# design.net
KiCad netlist of a schematic drawn in EasyEDA Pro
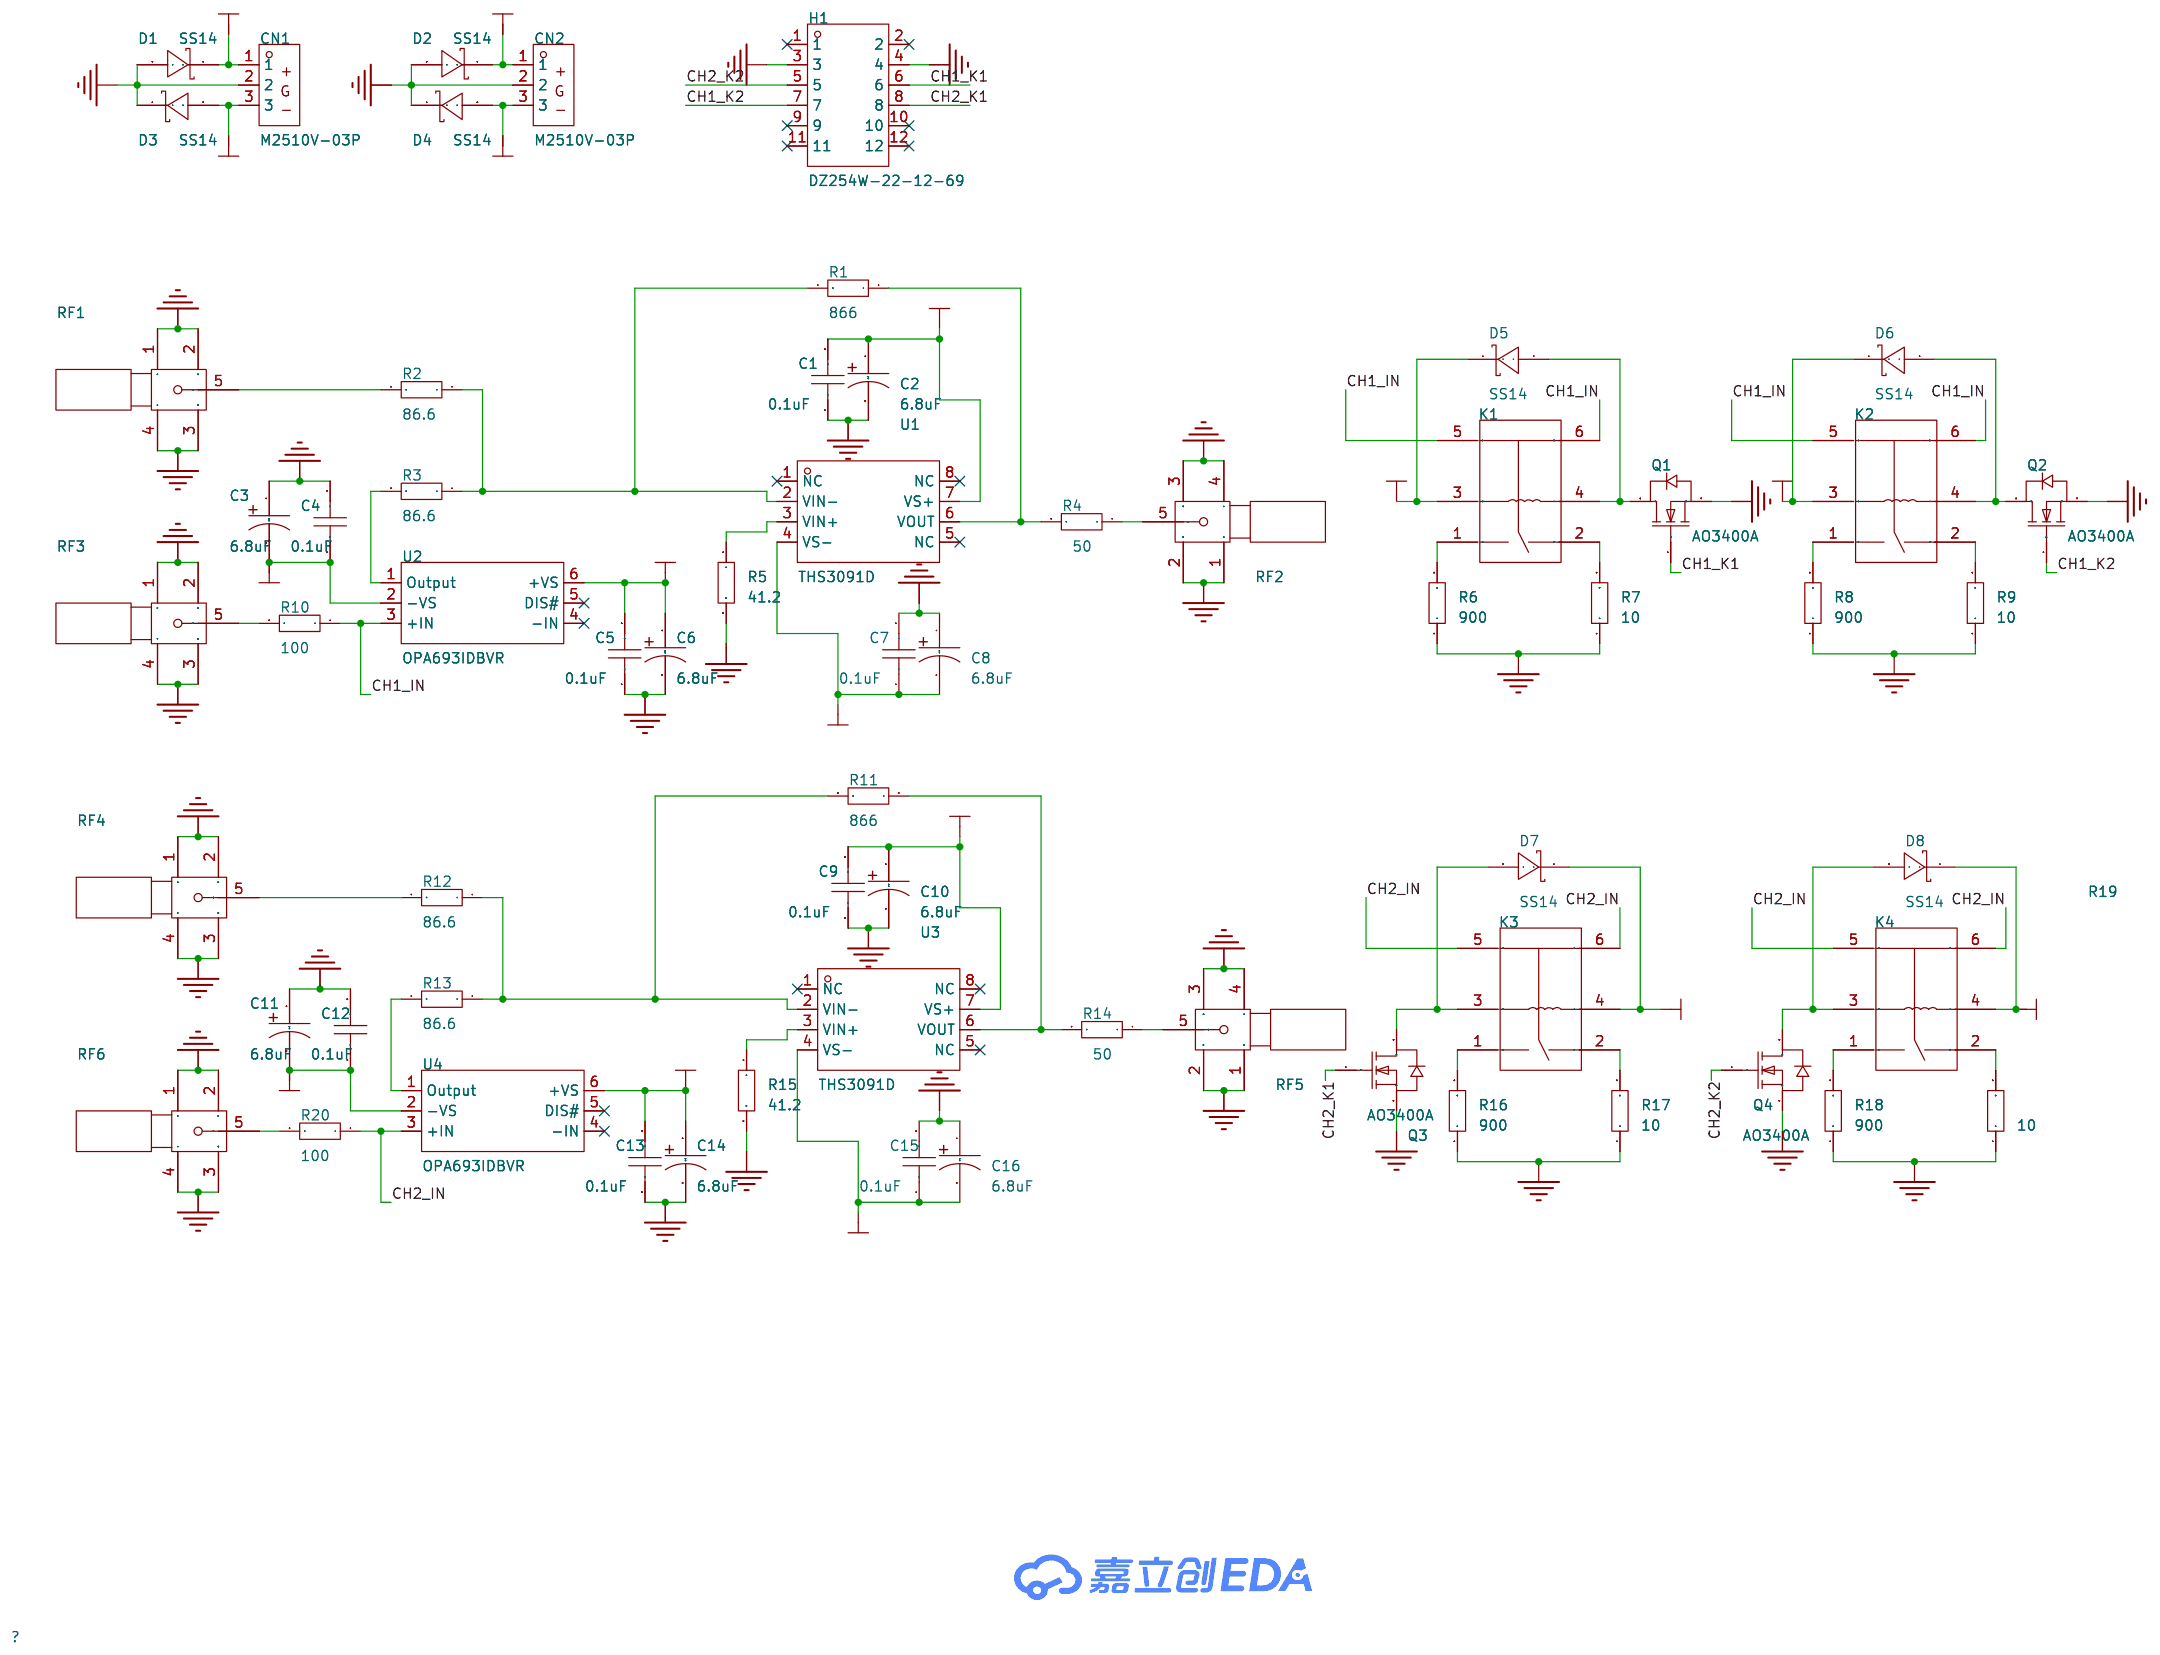
[diagram p0: schematic sheet]

(export (version "E")
  (design (tool "Eeschema 10.0.6"))
  (components
    (comp (ref "C1")
      (value "0.1uF")
      (footprint "easyedapro:C0603")
      (libsource (lib "easyedapro") (part "CapAcitance"))
    )
    (comp (ref "C2")
      (value "6.8uF")
      (footprint "easyedapro:CAP-SMD_L3.5-W2.8-R-RD")
      (description "容值:6.8uF;精度:±10%;额定电压:25V;等效串联电阻:2.8Ω@100kHz;")
      (fields
        (field (name "Manufacturer Part") "TPSC685K035R0350")
        (field (name "Manufacturer") "Kyocera AVX")
      )
      (libsource (lib "easyedapro") (part "TAJB685K025RNJ"))
    )
    (comp (ref "C3")
      (value "6.8uF")
      (footprint "easyedapro:CAP-SMD_L3.5-W2.8-R-RD")
      (description "容值:6.8uF;精度:±10%;额定电压:25V;等效串联电阻:2.8Ω@100kHz;")
      (fields
        (field (name "Manufacturer Part") "TPSC685K035R0350")
        (field (name "Manufacturer") "Kyocera AVX")
      )
      (libsource (lib "easyedapro") (part "TAJB685K025RNJ"))
    )
    (comp (ref "C4")
      (value "0.1uF")
      (footprint "easyedapro:C0603")
      (libsource (lib "easyedapro") (part "CapAcitance"))
    )
    (comp (ref "C5")
      (value "0.1uF")
      (footprint "easyedapro:C0603")
      (libsource (lib "easyedapro") (part "CapAcitance"))
    )
    (comp (ref "C6")
      (value "6.8uF")
      (footprint "easyedapro:CAP-SMD_L3.5-W2.8-R-RD")
      (description "容值:6.8uF;精度:±10%;额定电压:25V;等效串联电阻:2.8Ω@100kHz;")
      (fields
        (field (name "Manufacturer Part") "TPSC685K035R0350")
        (field (name "Manufacturer") "Kyocera AVX")
      )
      (libsource (lib "easyedapro") (part "TAJB685K025RNJ"))
    )
    (comp (ref "C7")
      (value "0.1uF")
      (footprint "easyedapro:C0603")
      (libsource (lib "easyedapro") (part "CapAcitance"))
    )
    (comp (ref "C8")
      (value "6.8uF")
      (footprint "easyedapro:CAP-SMD_L3.5-W2.8-R-RD")
      (description "容值:6.8uF;精度:±10%;额定电压:25V;等效串联电阻:2.8Ω@100kHz;")
      (fields
        (field (name "Manufacturer Part") "TPSC685K035R0350")
        (field (name "Manufacturer") "Kyocera AVX")
      )
      (libsource (lib "easyedapro") (part "TAJB685K025RNJ"))
    )
    (comp (ref "C9")
      (value "0.1uF")
      (footprint "easyedapro:C0603")
      (libsource (lib "easyedapro") (part "CapAcitance"))
    )
    (comp (ref "C10")
      (value "6.8uF")
      (footprint "easyedapro:CAP-SMD_L3.5-W2.8-R-RD")
      (description "容值:6.8uF;精度:±10%;额定电压:25V;等效串联电阻:2.8Ω@100kHz;")
      (fields
        (field (name "Manufacturer Part") "TPSC685K035R0350")
        (field (name "Manufacturer") "Kyocera AVX")
      )
      (libsource (lib "easyedapro") (part "TAJB685K025RNJ"))
    )
    (comp (ref "C11")
      (value "6.8uF")
      (footprint "easyedapro:CAP-SMD_L3.5-W2.8-R-RD")
      (description "容值:6.8uF;精度:±10%;额定电压:25V;等效串联电阻:2.8Ω@100kHz;")
      (fields
        (field (name "Manufacturer Part") "TPSC685K035R0350")
        (field (name "Manufacturer") "Kyocera AVX")
      )
      (libsource (lib "easyedapro") (part "TAJB685K025RNJ"))
    )
    (comp (ref "C12")
      (value "0.1uF")
      (footprint "easyedapro:C0603")
      (libsource (lib "easyedapro") (part "CapAcitance"))
    )
    (comp (ref "C13")
      (value "0.1uF")
      (footprint "easyedapro:C0603")
      (libsource (lib "easyedapro") (part "CapAcitance"))
    )
    (comp (ref "C14")
      (value "6.8uF")
      (footprint "easyedapro:CAP-SMD_L3.5-W2.8-R-RD")
      (description "容值:6.8uF;精度:±10%;额定电压:25V;等效串联电阻:2.8Ω@100kHz;")
      (fields
        (field (name "Manufacturer Part") "TPSC685K035R0350")
        (field (name "Manufacturer") "Kyocera AVX")
      )
      (libsource (lib "easyedapro") (part "TAJB685K025RNJ"))
    )
    (comp (ref "C15")
      (value "0.1uF")
      (footprint "easyedapro:C0603")
      (libsource (lib "easyedapro") (part "CapAcitance"))
    )
    (comp (ref "C16")
      (value "6.8uF")
      (footprint "easyedapro:CAP-SMD_L3.5-W2.8-R-RD")
      (description "容值:6.8uF;精度:±10%;额定电压:25V;等效串联电阻:2.8Ω@100kHz;")
      (fields
        (field (name "Manufacturer Part") "TPSC685K035R0350")
        (field (name "Manufacturer") "Kyocera AVX")
      )
      (libsource (lib "easyedapro") (part "TAJB685K025RNJ"))
    )
    (comp (ref "CN1")
      (value "M2510V-03P")
      (footprint "easyedapro:CONN-TH_M2510V-03P")
      (description "插针结构:1x3P;间距:2.54mm;安装方式:直插;参考系列:-;总PIN数:3P;排数:1;每排PIN数:3;行距:-;额定电流:3A;工作温度范围:-25°C~+85°C;")
      (fields (field (name "Manufacturer") "XFCN(兴飞)"))
      (libsource (lib "easyedapro") (part "M2510V-03P"))
    )
    (comp (ref "CN2")
      (value "M2510V-03P")
      (footprint "easyedapro:CONN-TH_M2510V-03P")
      (description "插针结构:1x3P;间距:2.54mm;安装方式:直插;参考系列:-;总PIN数:3P;排数:1;每排PIN数:3;行距:-;额定电流:3A;工作温度范围:-25°C~+85°C;")
      (fields (field (name "Manufacturer") "XFCN(兴飞)"))
      (libsource (lib "easyedapro") (part "M2510V-03P"))
    )
    (comp (ref "D1")
      (value "SS14")
      (footprint "easyedapro:SMA_L4.3-W2.6-LS5.2-RD")
      (description "正向压降(Vf):500mV@1A;直流反向耐压(Vr):40V;整流电流:1A;")
      (fields (field (name "Manufacturer") "onsemi(安森美)"))
      (libsource (lib "easyedapro") (part "SS14_C83852"))
    )
    (comp (ref "D2")
      (value "SS14")
      (footprint "easyedapro:SMA_L4.3-W2.6-LS5.2-RD")
      (description "正向压降(Vf):500mV@1A;直流反向耐压(Vr):40V;整流电流:1A;")
      (fields (field (name "Manufacturer") "onsemi(安森美)"))
      (libsource (lib "easyedapro") (part "SS14_C83852"))
    )
    (comp (ref "D3")
      (value "SS14")
      (footprint "easyedapro:SMA_L4.3-W2.6-LS5.2-RD")
      (description "正向压降(Vf):500mV@1A;直流反向耐压(Vr):40V;整流电流:1A;")
      (fields (field (name "Manufacturer") "onsemi(安森美)"))
      (libsource (lib "easyedapro") (part "SS14_C83852"))
    )
    (comp (ref "D4")
      (value "SS14")
      (footprint "easyedapro:SMA_L4.3-W2.6-LS5.2-RD")
      (description "正向压降(Vf):500mV@1A;直流反向耐压(Vr):40V;整流电流:1A;")
      (fields (field (name "Manufacturer") "onsemi(安森美)"))
      (libsource (lib "easyedapro") (part "SS14_C83852"))
    )
    (comp (ref "D5")
      (value "SS14")
      (footprint "easyedapro:SMA_L4.3-W2.6-LS5.2-RD")
      (description "正向压降(Vf):500mV@1A;直流反向耐压(Vr):40V;整流电流:1A;")
      (fields (field (name "Manufacturer") "onsemi(安森美)"))
      (libsource (lib "easyedapro") (part "SS14_C83852"))
    )
    (comp (ref "D6")
      (value "SS14")
      (footprint "easyedapro:SMA_L4.3-W2.6-LS5.2-RD")
      (description "正向压降(Vf):500mV@1A;直流反向耐压(Vr):40V;整流电流:1A;")
      (fields (field (name "Manufacturer") "onsemi(安森美)"))
      (libsource (lib "easyedapro") (part "SS14_C83852"))
    )
    (comp (ref "D7")
      (value "SS14")
      (footprint "easyedapro:SMA_L4.3-W2.6-LS5.2-RD")
      (description "正向压降(Vf):500mV@1A;直流反向耐压(Vr):40V;整流电流:1A;")
      (fields (field (name "Manufacturer") "onsemi(安森美)"))
      (libsource (lib "easyedapro") (part "SS14_C83852"))
    )
    (comp (ref "D8")
      (value "SS14")
      (footprint "easyedapro:SMA_L4.3-W2.6-LS5.2-RD")
      (description "正向压降(Vf):500mV@1A;直流反向耐压(Vr):40V;整流电流:1A;")
      (fields (field (name "Manufacturer") "onsemi(安森美)"))
      (libsource (lib "easyedapro") (part "SS14_C83852"))
    )
    (comp (ref "H1")
      (value "DZ254W-22-12-69")
      (footprint "easyedapro:HDR-TH_12P-P2.54-H-M-R2-C6-S2.54-W12.5")
      (fields (field (name "Manufacturer") "DEALON(德艺隆)"))
      (libsource (lib "easyedapro") (part "DZ254W-22-12-69"))
    )
    (comp (ref "K1")
      (value "HK4100F-DC5V-SHG")
      (footprint "easyedapro:RELAY-TH_HK4100F-DC5V-SHG")
      (description "线圈电压:-;触点形式:-;触点容量(电阻负载):-;最大切换电压:-;最大切换电流:-;")
      (fields (field (name "Manufacturer") "汇科"))
      (libsource (lib "easyedapro") (part "HK4100F-DC5V-SHG"))
    )
    (comp (ref "K2")
      (value "HK4100F-DC5V-SHG")
      (footprint "easyedapro:RELAY-TH_HK4100F-DC5V-SHG")
      (description "线圈电压:-;触点形式:-;触点容量(电阻负载):-;最大切换电压:-;最大切换电流:-;")
      (fields (field (name "Manufacturer") "汇科"))
      (libsource (lib "easyedapro") (part "HK4100F-DC5V-SHG"))
    )
    (comp (ref "K3")
      (value "HK4100F-DC5V-SHG")
      (footprint "easyedapro:RELAY-TH_HK4100F-DC5V-SHG")
      (description "线圈电压:-;触点形式:-;触点容量(电阻负载):-;最大切换电压:-;最大切换电流:-;")
      (fields (field (name "Manufacturer") "汇科"))
      (libsource (lib "easyedapro") (part "HK4100F-DC5V-SHG"))
    )
    (comp (ref "K4")
      (value "HK4100F-DC5V-SHG")
      (footprint "easyedapro:RELAY-TH_HK4100F-DC5V-SHG")
      (description "线圈电压:-;触点形式:-;触点容量(电阻负载):-;最大切换电压:-;最大切换电流:-;")
      (fields (field (name "Manufacturer") "汇科"))
      (libsource (lib "easyedapro") (part "HK4100F-DC5V-SHG"))
    )
    (comp (ref "Q1")
      (value "AO3400A")
      (footprint "easyedapro:SOT-23-3_L2.9-W1.3-P1.90-LS2.4-BR")
      (fields (field (name "Manufacturer") "AOS"))
      (libsource (lib "easyedapro") (part "AO3400A"))
    )
    (comp (ref "Q2")
      (value "AO3400A")
      (footprint "easyedapro:SOT-23-3_L2.9-W1.3-P1.90-LS2.4-BR")
      (fields (field (name "Manufacturer") "AOS"))
      (libsource (lib "easyedapro") (part "AO3400A"))
    )
    (comp (ref "Q3")
      (value "AO3400A")
      (footprint "easyedapro:SOT-23-3_L2.9-W1.3-P1.90-LS2.4-BR")
      (fields (field (name "Manufacturer") "AOS"))
      (libsource (lib "easyedapro") (part "AO3400A"))
    )
    (comp (ref "Q4")
      (value "AO3400A")
      (footprint "easyedapro:SOT-23-3_L2.9-W1.3-P1.90-LS2.4-BR")
      (fields (field (name "Manufacturer") "AOS"))
      (libsource (lib "easyedapro") (part "AO3400A"))
    )
    (comp (ref "R1") (value "866") (footprint "easyedapro:R0603") (libsource (lib "easyedapro") (part "电阻")))
    (comp (ref "R2") (value "86.6") (footprint "easyedapro:R0603") (libsource (lib "easyedapro") (part "电阻")))
    (comp (ref "R3") (value "86.6") (footprint "easyedapro:R0603") (libsource (lib "easyedapro") (part "电阻")))
    (comp (ref "R4") (value "50") (footprint "easyedapro:R0603") (libsource (lib "easyedapro") (part "电阻")))
    (comp (ref "R5") (value "41.2") (footprint "easyedapro:R0603") (libsource (lib "easyedapro") (part "电阻")))
    (comp (ref "R6") (value "900") (footprint "easyedapro:R0603") (libsource (lib "easyedapro") (part "电阻")))
    (comp (ref "R7") (value "10") (footprint "easyedapro:R0603") (libsource (lib "easyedapro") (part "电阻")))
    (comp (ref "R8") (value "900") (footprint "easyedapro:R0603") (libsource (lib "easyedapro") (part "电阻")))
    (comp (ref "R9") (value "10") (footprint "easyedapro:R0603") (libsource (lib "easyedapro") (part "电阻")))
    (comp (ref "R10") (value "100") (footprint "easyedapro:R0603") (libsource (lib "easyedapro") (part "电阻")))
    (comp (ref "R11") (value "866") (footprint "easyedapro:R0603") (libsource (lib "easyedapro") (part "电阻")))
    (comp (ref "R12")
      (value "86.6")
      (footprint "easyedapro:R0603")
      (libsource (lib "easyedapro") (part "电阻"))
    )
    (comp (ref "R13")
      (value "86.6")
      (footprint "easyedapro:R0603")
      (libsource (lib "easyedapro") (part "电阻"))
    )
    (comp (ref "R14") (value "50") (footprint "easyedapro:R0603") (libsource (lib "easyedapro") (part "电阻")))
    (comp (ref "R15")
      (value "41.2")
      (footprint "easyedapro:R0603")
      (libsource (lib "easyedapro") (part "电阻"))
    )
    (comp (ref "R16") (value "900") (footprint "easyedapro:R0603") (libsource (lib "easyedapro") (part "电阻")))
    (comp (ref "R17") (value "10") (footprint "easyedapro:R0603") (libsource (lib "easyedapro") (part "电阻")))
    (comp (ref "R18") (value "900") (footprint "easyedapro:R0603") (libsource (lib "easyedapro") (part "电阻")))
    (comp (ref "R19") (value "10") (footprint "easyedapro:R0603") (libsource (lib "easyedapro") (part "电阻")))
    (comp (ref "R20") (value "100") (footprint "easyedapro:R0603") (libsource (lib "easyedapro") (part "电阻")))
    (comp (ref "RF1")
      (value "BWSMA-KE-P001")
      (footprint "easyedapro:SMA-SMD_BWSMA-KE-P001")
      (description "连接器类型:板端;接口类型:内孔;端口数量:1;接口直径:5.2mm;接口长度/高度:-;频率-最大值:-;射频系列:SMA;阻抗:50Ω;样式:偏脚;工作温度范围:-;")
      (fields (field (name "Manufacturer") "BAT WIRELESS(蝙蝠无线)"))
      (libsource (lib "easyedapro") (part "BWSMA-KE-P001"))
    )
    (comp (ref "RF2")
      (value "BWSMA-KE-P001")
      (footprint "easyedapro:SMA-SMD_BWSMA-KE-P001")
      (description "连接器类型:板端;接口类型:内孔;端口数量:1;接口直径:5.2mm;接口长度/高度:-;频率-最大值:-;射频系列:SMA;阻抗:50Ω;样式:偏脚;工作温度范围:-;")
      (fields (field (name "Manufacturer") "BAT WIRELESS(蝙蝠无线)"))
      (libsource (lib "easyedapro") (part "BWSMA-KE-P001"))
    )
    (comp (ref "RF3")
      (value "BWSMA-KE-P001")
      (footprint "easyedapro:SMA-SMD_BWSMA-KE-P001")
      (description "连接器类型:板端;接口类型:内孔;端口数量:1;接口直径:5.2mm;接口长度/高度:-;频率-最大值:-;射频系列:SMA;阻抗:50Ω;样式:偏脚;工作温度范围:-;")
      (fields (field (name "Manufacturer") "BAT WIRELESS(蝙蝠无线)"))
      (libsource (lib "easyedapro") (part "BWSMA-KE-P001"))
    )
    (comp (ref "RF4")
      (value "BWSMA-KE-P001")
      (footprint "easyedapro:SMA-SMD_BWSMA-KE-P001")
      (description "连接器类型:板端;接口类型:内孔;端口数量:1;接口直径:5.2mm;接口长度/高度:-;频率-最大值:-;射频系列:SMA;阻抗:50Ω;样式:偏脚;工作温度范围:-;")
      (fields (field (name "Manufacturer") "BAT WIRELESS(蝙蝠无线)"))
      (libsource (lib "easyedapro") (part "BWSMA-KE-P001"))
    )
    (comp (ref "RF5")
      (value "BWSMA-KE-P001")
      (footprint "easyedapro:SMA-SMD_BWSMA-KE-P001")
      (description "连接器类型:板端;接口类型:内孔;端口数量:1;接口直径:5.2mm;接口长度/高度:-;频率-最大值:-;射频系列:SMA;阻抗:50Ω;样式:偏脚;工作温度范围:-;")
      (fields (field (name "Manufacturer") "BAT WIRELESS(蝙蝠无线)"))
      (libsource (lib "easyedapro") (part "BWSMA-KE-P001"))
    )
    (comp (ref "RF6")
      (value "BWSMA-KE-P001")
      (footprint "easyedapro:SMA-SMD_BWSMA-KE-P001")
      (description "连接器类型:板端;接口类型:内孔;端口数量:1;接口直径:5.2mm;接口长度/高度:-;频率-最大值:-;射频系列:SMA;阻抗:50Ω;样式:偏脚;工作温度范围:-;")
      (fields (field (name "Manufacturer") "BAT WIRELESS(蝙蝠无线)"))
      (libsource (lib "easyedapro") (part "BWSMA-KE-P001"))
    )
    (comp (ref "U1")
      (value "THS3091D")
      (footprint "easyedapro:SOIC-8_L4.9-W3.9-P1.27-LS6.0-TR")
      (description "放大器数:单路;增益带宽积(GBP):-;输入偏置电流(Ib):4uA;压摆率(SR):7300V/us;带宽(-3db):235MHz;")
      (fields (field (name "Manufacturer") "TI(德州仪器)"))
      (libsource (lib "easyedapro") (part "THS3091D"))
    )
    (comp (ref "U2")
      (value "OPA693IDBVR")
      (footprint "easyedapro:SOT-23-6_L2.9-W1.6-P0.95-LS2.8-BL")
      (description "放大器数:单路;带宽(-3db):1.4GHz;压摆率(SR):2500V/us;输入偏置电流(Ib):13mA;")
      (fields (field (name "Manufacturer") "TI(德州仪器)"))
      (libsource (lib "easyedapro") (part "OPA693IDBVR"))
    )
    (comp (ref "U3")
      (value "THS3091D")
      (footprint "easyedapro:SOIC-8_L4.9-W3.9-P1.27-LS6.0-TR")
      (description "放大器数:单路;增益带宽积(GBP):-;输入偏置电流(Ib):4uA;压摆率(SR):7300V/us;带宽(-3db):235MHz;")
      (fields (field (name "Manufacturer") "TI(德州仪器)"))
      (libsource (lib "easyedapro") (part "THS3091D"))
    )
    (comp (ref "U4")
      (value "OPA693IDBVR")
      (footprint "easyedapro:SOT-23-6_L2.9-W1.6-P0.95-LS2.8-BL")
      (description "放大器数:单路;带宽(-3db):1.4GHz;压摆率(SR):2500V/us;输入偏置电流(Ib):13mA;")
      (fields (field (name "Manufacturer") "TI(德州仪器)"))
      (libsource (lib "easyedapro") (part "OPA693IDBVR"))
    )
  )
  (nets
    (net (code "1") (name "+5V") (class "Default")
      (node (ref "C13") (pin "2") (pinfunction "2_2") (pintype "input"))
      (node (ref "C14") (pin "1") (pinfunction "1_1") (pintype "unspecified"))
      (node (ref "C5") (pin "2") (pinfunction "2_2") (pintype "input"))
      (node (ref "C6") (pin "1") (pinfunction "1_1") (pintype "unspecified"))
      (node (ref "CN2") (pin "1") (pinfunction "1_1") (pintype "unspecified"))
      (node (ref "D2") (pin "1") (pinfunction "K_1") (pintype "unspecified"))
      (node (ref "D5") (pin "1") (pinfunction "K_1") (pintype "unspecified"))
      (node (ref "D6") (pin "1") (pinfunction "K_1") (pintype "unspecified"))
      (node (ref "D7") (pin "1") (pinfunction "K_1") (pintype "unspecified"))
      (node (ref "D8") (pin "1") (pinfunction "K_1") (pintype "unspecified"))
      (node (ref "K1") (pin "3") (pinfunction "3_3") (pintype "unspecified"))
      (node (ref "K2") (pin "3") (pinfunction "3_3") (pintype "unspecified"))
      (node (ref "K3") (pin "4") (pinfunction "4_4") (pintype "unspecified"))
      (node (ref "K4") (pin "4") (pinfunction "4_4") (pintype "unspecified"))
      (node (ref "U2") (pin "6") (pinfunction "+VS_6") (pintype "unspecified"))
      (node (ref "U4") (pin "6") (pinfunction "+VS_6") (pintype "unspecified"))
    )
    (net (code "2") (name "+12V") (class "Default")
      (node (ref "C1") (pin "2") (pinfunction "2_2") (pintype "input"))
      (node (ref "C10") (pin "1") (pinfunction "1_1") (pintype "unspecified"))
      (node (ref "C2") (pin "1") (pinfunction "1_1") (pintype "unspecified"))
      (node (ref "C9") (pin "2") (pinfunction "2_2") (pintype "input"))
      (node (ref "CN1") (pin "1") (pinfunction "1_1") (pintype "unspecified"))
      (node (ref "D1") (pin "1") (pinfunction "K_1") (pintype "unspecified"))
      (node (ref "U1") (pin "7") (pinfunction "VS+_7") (pintype "unspecified"))
      (node (ref "U3") (pin "7") (pinfunction "VS+_7") (pintype "unspecified"))
    )
    (net (code "3") (name "-5V") (class "Default")
      (node (ref "C11") (pin "2") (pinfunction "2_2") (pintype "unspecified"))
      (node (ref "C12") (pin "1") (pinfunction "1_1") (pintype "input"))
      (node (ref "C3") (pin "2") (pinfunction "2_2") (pintype "unspecified"))
      (node (ref "C4") (pin "1") (pinfunction "1_1") (pintype "input"))
      (node (ref "CN2") (pin "3") (pinfunction "3_3") (pintype "unspecified"))
      (node (ref "D4") (pin "2") (pinfunction "A_2") (pintype "unspecified"))
      (node (ref "U2") (pin "2") (pinfunction "−VS_2") (pintype "unspecified"))
      (node (ref "U4") (pin "2") (pinfunction "−VS_2") (pintype "unspecified"))
    )
    (net (code "4") (name "-12V") (class "Default")
      (node (ref "C15") (pin "1") (pinfunction "1_1") (pintype "input"))
      (node (ref "C16") (pin "2") (pinfunction "2_2") (pintype "unspecified"))
      (node (ref "C7") (pin "1") (pinfunction "1_1") (pintype "input"))
      (node (ref "C8") (pin "2") (pinfunction "2_2") (pintype "unspecified"))
      (node (ref "CN1") (pin "3") (pinfunction "3_3") (pintype "unspecified"))
      (node (ref "D3") (pin "2") (pinfunction "A_2") (pintype "unspecified"))
      (node (ref "U1") (pin "4") (pinfunction "VS-_4") (pintype "unspecified"))
      (node (ref "U3") (pin "4") (pinfunction "VS-_4") (pintype "unspecified"))
    )
    (net (code "5") (name "/CH1_IN") (class "Default")
      (node (ref "K1") (pin "5") (pinfunction "5_5") (pintype "unspecified"))
      (node (ref "K1") (pin "6") (pinfunction "6_6") (pintype "unspecified"))
      (node (ref "K2") (pin "5") (pinfunction "5_5") (pintype "unspecified"))
      (node (ref "K2") (pin "6") (pinfunction "6_6") (pintype "unspecified"))
      (node (ref "R10") (pin "1") (pinfunction "1_1") (pintype "input"))
      (node (ref "U2") (pin "3") (pinfunction "+IN_3") (pintype "unspecified"))
    )
    (net (code "6") (name "/CH1_K1") (class "Default")
      (node (ref "H1") (pin "6") (pinfunction "6_6") (pintype "input"))
      (node (ref "Q1") (pin "1") (pinfunction "G_1") (pintype "unspecified"))
    )
    (net (code "7") (name "/CH1_K2") (class "Default")
      (node (ref "H1") (pin "7") (pinfunction "7_7") (pintype "input"))
      (node (ref "Q2") (pin "1") (pinfunction "G_1") (pintype "unspecified"))
    )
    (net (code "8") (name "/CH2_IN") (class "Default")
      (node (ref "K3") (pin "5") (pinfunction "5_5") (pintype "unspecified"))
      (node (ref "K3") (pin "6") (pinfunction "6_6") (pintype "unspecified"))
      (node (ref "K4") (pin "5") (pinfunction "5_5") (pintype "unspecified"))
      (node (ref "K4") (pin "6") (pinfunction "6_6") (pintype "unspecified"))
      (node (ref "R20") (pin "1") (pinfunction "1_1") (pintype "input"))
      (node (ref "U4") (pin "3") (pinfunction "+IN_3") (pintype "unspecified"))
    )
    (net (code "9") (name "/CH2_K1") (class "Default")
      (node (ref "H1") (pin "8") (pinfunction "8_8") (pintype "input"))
      (node (ref "Q3") (pin "1") (pinfunction "G_1") (pintype "unspecified"))
    )
    (net (code "10") (name "/CH2_K2") (class "Default")
      (node (ref "H1") (pin "5") (pinfunction "5_5") (pintype "input"))
      (node (ref "Q4") (pin "1") (pinfunction "G_1") (pintype "unspecified"))
    )
    (net (code "11") (name "GND") (class "Default")
      (node (ref "C1") (pin "1") (pinfunction "1_1") (pintype "input"))
      (node (ref "C10") (pin "2") (pinfunction "2_2") (pintype "unspecified"))
      (node (ref "C11") (pin "1") (pinfunction "1_1") (pintype "unspecified"))
      (node (ref "C12") (pin "2") (pinfunction "2_2") (pintype "input"))
      (node (ref "C13") (pin "1") (pinfunction "1_1") (pintype "input"))
      (node (ref "C14") (pin "2") (pinfunction "2_2") (pintype "unspecified"))
      (node (ref "C15") (pin "2") (pinfunction "2_2") (pintype "input"))
      (node (ref "C16") (pin "1") (pinfunction "1_1") (pintype "unspecified"))
      (node (ref "C2") (pin "2") (pinfunction "2_2") (pintype "unspecified"))
      (node (ref "C3") (pin "1") (pinfunction "1_1") (pintype "unspecified"))
      (node (ref "C4") (pin "2") (pinfunction "2_2") (pintype "input"))
      (node (ref "C5") (pin "1") (pinfunction "1_1") (pintype "input"))
      (node (ref "C6") (pin "2") (pinfunction "2_2") (pintype "unspecified"))
      (node (ref "C7") (pin "2") (pinfunction "2_2") (pintype "input"))
      (node (ref "C8") (pin "1") (pinfunction "1_1") (pintype "unspecified"))
      (node (ref "C9") (pin "1") (pinfunction "1_1") (pintype "input"))
      (node (ref "CN1") (pin "2") (pinfunction "2_2") (pintype "unspecified"))
      (node (ref "CN2") (pin "2") (pinfunction "2_2") (pintype "unspecified"))
      (node (ref "D1") (pin "2") (pinfunction "A_2") (pintype "unspecified"))
      (node (ref "D2") (pin "2") (pinfunction "A_2") (pintype "unspecified"))
      (node (ref "D3") (pin "1") (pinfunction "K_1") (pintype "unspecified"))
      (node (ref "D4") (pin "1") (pinfunction "K_1") (pintype "unspecified"))
      (node (ref "H1") (pin "3") (pinfunction "3_3") (pintype "input"))
      (node (ref "H1") (pin "4") (pinfunction "4_4") (pintype "input"))
      (node (ref "Q1") (pin "2") (pinfunction "S_2") (pintype "unspecified"))
      (node (ref "Q2") (pin "2") (pinfunction "S_2") (pintype "unspecified"))
      (node (ref "Q3") (pin "2") (pinfunction "S_2") (pintype "unspecified"))
      (node (ref "Q4") (pin "2") (pinfunction "S_2") (pintype "unspecified"))
      (node (ref "R15") (pin "2") (pinfunction "2_2") (pintype "input"))
      (node (ref "R16") (pin "1") (pinfunction "1_1") (pintype "input"))
      (node (ref "R17") (pin "1") (pinfunction "1_1") (pintype "input"))
      (node (ref "R18") (pin "1") (pinfunction "1_1") (pintype "input"))
      (node (ref "R19") (pin "1") (pinfunction "1_1") (pintype "input"))
      (node (ref "R5") (pin "2") (pinfunction "2_2") (pintype "input"))
      (node (ref "R6") (pin "1") (pinfunction "1_1") (pintype "input"))
      (node (ref "R7") (pin "1") (pinfunction "1_1") (pintype "input"))
      (node (ref "R8") (pin "1") (pinfunction "1_1") (pintype "input"))
      (node (ref "R9") (pin "1") (pinfunction "1_1") (pintype "input"))
      (node (ref "RF1") (pin "1") (pinfunction "1_1") (pintype "unspecified"))
      (node (ref "RF1") (pin "2") (pinfunction "2_2") (pintype "unspecified"))
      (node (ref "RF1") (pin "3") (pinfunction "3_3") (pintype "unspecified"))
      (node (ref "RF1") (pin "4") (pinfunction "4_4") (pintype "unspecified"))
      (node (ref "RF2") (pin "1") (pinfunction "1_1") (pintype "unspecified"))
      (node (ref "RF2") (pin "2") (pinfunction "2_2") (pintype "unspecified"))
      (node (ref "RF2") (pin "3") (pinfunction "3_3") (pintype "unspecified"))
      (node (ref "RF2") (pin "4") (pinfunction "4_4") (pintype "unspecified"))
      (node (ref "RF3") (pin "1") (pinfunction "1_1") (pintype "unspecified"))
      (node (ref "RF3") (pin "2") (pinfunction "2_2") (pintype "unspecified"))
      (node (ref "RF3") (pin "3") (pinfunction "3_3") (pintype "unspecified"))
      (node (ref "RF3") (pin "4") (pinfunction "4_4") (pintype "unspecified"))
      (node (ref "RF4") (pin "1") (pinfunction "1_1") (pintype "unspecified"))
      (node (ref "RF4") (pin "2") (pinfunction "2_2") (pintype "unspecified"))
      (node (ref "RF4") (pin "3") (pinfunction "3_3") (pintype "unspecified"))
      (node (ref "RF4") (pin "4") (pinfunction "4_4") (pintype "unspecified"))
      (node (ref "RF5") (pin "1") (pinfunction "1_1") (pintype "unspecified"))
      (node (ref "RF5") (pin "2") (pinfunction "2_2") (pintype "unspecified"))
      (node (ref "RF5") (pin "3") (pinfunction "3_3") (pintype "unspecified"))
      (node (ref "RF5") (pin "4") (pinfunction "4_4") (pintype "unspecified"))
      (node (ref "RF6") (pin "1") (pinfunction "1_1") (pintype "unspecified"))
      (node (ref "RF6") (pin "2") (pinfunction "2_2") (pintype "unspecified"))
      (node (ref "RF6") (pin "3") (pinfunction "3_3") (pintype "unspecified"))
      (node (ref "RF6") (pin "4") (pinfunction "4_4") (pintype "unspecified"))
    )
    (net (code "12") (name "Net-(D5-A)") (class "Default")
      (node (ref "D5") (pin "2") (pinfunction "A_2") (pintype "unspecified"))
      (node (ref "K1") (pin "4") (pinfunction "4_4") (pintype "unspecified"))
      (node (ref "Q1") (pin "3") (pinfunction "D_3") (pintype "unspecified"))
    )
    (net (code "13") (name "Net-(D6-A)") (class "Default")
      (node (ref "D6") (pin "2") (pinfunction "A_2") (pintype "unspecified"))
      (node (ref "K2") (pin "4") (pinfunction "4_4") (pintype "unspecified"))
      (node (ref "Q2") (pin "3") (pinfunction "D_3") (pintype "unspecified"))
    )
    (net (code "14") (name "Net-(D7-A)") (class "Default")
      (node (ref "D7") (pin "2") (pinfunction "A_2") (pintype "unspecified"))
      (node (ref "K3") (pin "3") (pinfunction "3_3") (pintype "unspecified"))
      (node (ref "Q3") (pin "3") (pinfunction "D_3") (pintype "unspecified"))
    )
    (net (code "15") (name "Net-(D8-A)") (class "Default")
      (node (ref "D8") (pin "2") (pinfunction "A_2") (pintype "unspecified"))
      (node (ref "K4") (pin "3") (pinfunction "3_3") (pintype "unspecified"))
      (node (ref "Q4") (pin "3") (pinfunction "D_3") (pintype "unspecified"))
    )
    (net (code "16") (name "Net-(K1-Pad1)") (class "Default")
      (node (ref "K1") (pin "1") (pinfunction "1_1") (pintype "unspecified"))
      (node (ref "R6") (pin "2") (pinfunction "2_2") (pintype "input"))
    )
    (net (code "17") (name "Net-(K1-Pad2)") (class "Default")
      (node (ref "K1") (pin "2") (pinfunction "2_2") (pintype "unspecified"))
      (node (ref "R7") (pin "2") (pinfunction "2_2") (pintype "input"))
    )
    (net (code "18") (name "Net-(K2-Pad1)") (class "Default")
      (node (ref "K2") (pin "1") (pinfunction "1_1") (pintype "unspecified"))
      (node (ref "R8") (pin "2") (pinfunction "2_2") (pintype "input"))
    )
    (net (code "19") (name "Net-(K2-Pad2)") (class "Default")
      (node (ref "K2") (pin "2") (pinfunction "2_2") (pintype "unspecified"))
      (node (ref "R9") (pin "2") (pinfunction "2_2") (pintype "input"))
    )
    (net (code "20") (name "Net-(K3-Pad1)") (class "Default")
      (node (ref "K3") (pin "1") (pinfunction "1_1") (pintype "unspecified"))
      (node (ref "R16") (pin "2") (pinfunction "2_2") (pintype "input"))
    )
    (net (code "21") (name "Net-(K3-Pad2)") (class "Default")
      (node (ref "K3") (pin "2") (pinfunction "2_2") (pintype "unspecified"))
      (node (ref "R17") (pin "2") (pinfunction "2_2") (pintype "input"))
    )
    (net (code "22") (name "Net-(K4-Pad1)") (class "Default")
      (node (ref "K4") (pin "1") (pinfunction "1_1") (pintype "unspecified"))
      (node (ref "R18") (pin "2") (pinfunction "2_2") (pintype "input"))
    )
    (net (code "23") (name "Net-(K4-Pad2)") (class "Default")
      (node (ref "K4") (pin "2") (pinfunction "2_2") (pintype "unspecified"))
      (node (ref "R19") (pin "2") (pinfunction "2_2") (pintype "input"))
    )
    (net (code "24") (name "Net-(R2-Pad2)") (class "Default")
      (node (ref "R2") (pin "2") (pinfunction "2_2") (pintype "input"))
      (node (ref "RF1") (pin "5") (pinfunction "5_5") (pintype "unspecified"))
    )
    (net (code "25") (name "Net-(R4-Pad1)") (class "Default")
      (node (ref "R4") (pin "1") (pinfunction "1_1") (pintype "input"))
      (node (ref "RF2") (pin "5") (pinfunction "5_5") (pintype "unspecified"))
    )
    (net (code "26") (name "Net-(R10-Pad2)") (class "Default")
      (node (ref "R10") (pin "2") (pinfunction "2_2") (pintype "input"))
      (node (ref "RF3") (pin "5") (pinfunction "5_5") (pintype "unspecified"))
    )
    (net (code "27") (name "Net-(R12-Pad2)") (class "Default")
      (node (ref "R12") (pin "2") (pinfunction "2_2") (pintype "input"))
      (node (ref "RF4") (pin "5") (pinfunction "5_5") (pintype "unspecified"))
    )
    (net (code "28") (name "Net-(R14-Pad1)") (class "Default")
      (node (ref "R14") (pin "1") (pinfunction "1_1") (pintype "input"))
      (node (ref "RF5") (pin "5") (pinfunction "5_5") (pintype "unspecified"))
    )
    (net (code "29") (name "Net-(R20-Pad2)") (class "Default")
      (node (ref "R20") (pin "2") (pinfunction "2_2") (pintype "input"))
      (node (ref "RF6") (pin "5") (pinfunction "5_5") (pintype "unspecified"))
    )
    (net (code "30") (name "Net-(U1-VIN+)") (class "Default")
      (node (ref "R5") (pin "1") (pinfunction "1_1") (pintype "input"))
      (node (ref "U1") (pin "3") (pinfunction "VIN+_3") (pintype "unspecified"))
    )
    (net (code "31") (name "Net-(U1-VIN-)") (class "Default")
      (node (ref "R1") (pin "2") (pinfunction "2_2") (pintype "input"))
      (node (ref "R2") (pin "1") (pinfunction "1_1") (pintype "input"))
      (node (ref "R3") (pin "1") (pinfunction "1_1") (pintype "input"))
      (node (ref "U1") (pin "2") (pinfunction "VIN-_2") (pintype "unspecified"))
    )
    (net (code "32") (name "Net-(U1-VOUT)") (class "Default")
      (node (ref "R1") (pin "1") (pinfunction "1_1") (pintype "input"))
      (node (ref "R4") (pin "2") (pinfunction "2_2") (pintype "input"))
      (node (ref "U1") (pin "6") (pinfunction "VOUT_6") (pintype "unspecified"))
    )
    (net (code "33") (name "Net-(U2-Output)") (class "Default")
      (node (ref "R3") (pin "2") (pinfunction "2_2") (pintype "input"))
      (node (ref "U2") (pin "1") (pinfunction "Output_1") (pintype "unspecified"))
    )
    (net (code "34") (name "Net-(U3-VIN+)") (class "Default")
      (node (ref "R15") (pin "1") (pinfunction "1_1") (pintype "input"))
      (node (ref "U3") (pin "3") (pinfunction "VIN+_3") (pintype "unspecified"))
    )
    (net (code "35") (name "Net-(U3-VIN-)") (class "Default")
      (node (ref "R11") (pin "2") (pinfunction "2_2") (pintype "input"))
      (node (ref "R12") (pin "1") (pinfunction "1_1") (pintype "input"))
      (node (ref "R13") (pin "1") (pinfunction "1_1") (pintype "input"))
      (node (ref "U3") (pin "2") (pinfunction "VIN-_2") (pintype "unspecified"))
    )
    (net (code "36") (name "Net-(U3-VOUT)") (class "Default")
      (node (ref "R11") (pin "1") (pinfunction "1_1") (pintype "input"))
      (node (ref "R14") (pin "2") (pinfunction "2_2") (pintype "input"))
      (node (ref "U3") (pin "6") (pinfunction "VOUT_6") (pintype "unspecified"))
    )
    (net (code "37") (name "Net-(U4-Output)") (class "Default")
      (node (ref "R13") (pin "2") (pinfunction "2_2") (pintype "input"))
      (node (ref "U4") (pin "1") (pinfunction "Output_1") (pintype "unspecified"))
    )
    (net (code "38") (name "unconnected-(H1-Pad1)") (class "Default")
      (node (ref "H1") (pin "1") (pinfunction "1_1") (pintype "input+no_connect"))
    )
    (net (code "39") (name "unconnected-(H1-Pad2)") (class "Default")
      (node (ref "H1") (pin "2") (pinfunction "2_2") (pintype "input+no_connect"))
    )
    (net (code "40") (name "unconnected-(H1-Pad9)") (class "Default")
      (node (ref "H1") (pin "9") (pinfunction "9_9") (pintype "input+no_connect"))
    )
    (net (code "41") (name "unconnected-(H1-Pad10)") (class "Default")
      (node (ref "H1") (pin "10") (pinfunction "10_10") (pintype "input+no_connect"))
    )
    (net (code "42") (name "unconnected-(H1-Pad11)") (class "Default")
      (node (ref "H1") (pin "11") (pinfunction "11_11") (pintype "input+no_connect"))
    )
    (net (code "43") (name "unconnected-(H1-Pad12)") (class "Default")
      (node (ref "H1") (pin "12") (pinfunction "12_12") (pintype "input+no_connect"))
    )
    (net (code "44") (name "unconnected-(U1-NC-Pad1)") (class "Default")
      (node (ref "U1") (pin "1") (pinfunction "NC_1") (pintype "unspecified+no_connect"))
    )
    (net (code "45") (name "unconnected-(U1-NC-Pad5)") (class "Default")
      (node (ref "U1") (pin "5") (pinfunction "NC_5") (pintype "unspecified+no_connect"))
    )
    (net (code "46") (name "unconnected-(U1-NC-Pad8)") (class "Default")
      (node (ref "U1") (pin "8") (pinfunction "NC_8") (pintype "unspecified+no_connect"))
    )
    (net (code "47") (name "unconnected-(U2-DIS#-Pad5)") (class "Default")
      (node (ref "U2") (pin "5") (pinfunction "DIS#_5") (pintype "unspecified+no_connect"))
    )
    (net (code "48") (name "unconnected-(U2-−IN-Pad4)") (class "Default")
      (node (ref "U2") (pin "4") (pinfunction "−IN_4") (pintype "unspecified+no_connect"))
    )
    (net (code "49") (name "unconnected-(U3-NC-Pad1)") (class "Default")
      (node (ref "U3") (pin "1") (pinfunction "NC_1") (pintype "unspecified+no_connect"))
    )
    (net (code "50") (name "unconnected-(U3-NC-Pad5)") (class "Default")
      (node (ref "U3") (pin "5") (pinfunction "NC_5") (pintype "unspecified+no_connect"))
    )
    (net (code "51") (name "unconnected-(U3-NC-Pad8)") (class "Default")
      (node (ref "U3") (pin "8") (pinfunction "NC_8") (pintype "unspecified+no_connect"))
    )
    (net (code "52") (name "unconnected-(U4-DIS#-Pad5)") (class "Default")
      (node (ref "U4") (pin "5") (pinfunction "DIS#_5") (pintype "unspecified+no_connect"))
    )
    (net (code "53") (name "unconnected-(U4-−IN-Pad4)") (class "Default")
      (node (ref "U4") (pin "4") (pinfunction "−IN_4") (pintype "unspecified+no_connect"))
    )
  )
)
